# Sheet.net
KiCad netlist of a schematic drawn in Altium Designer
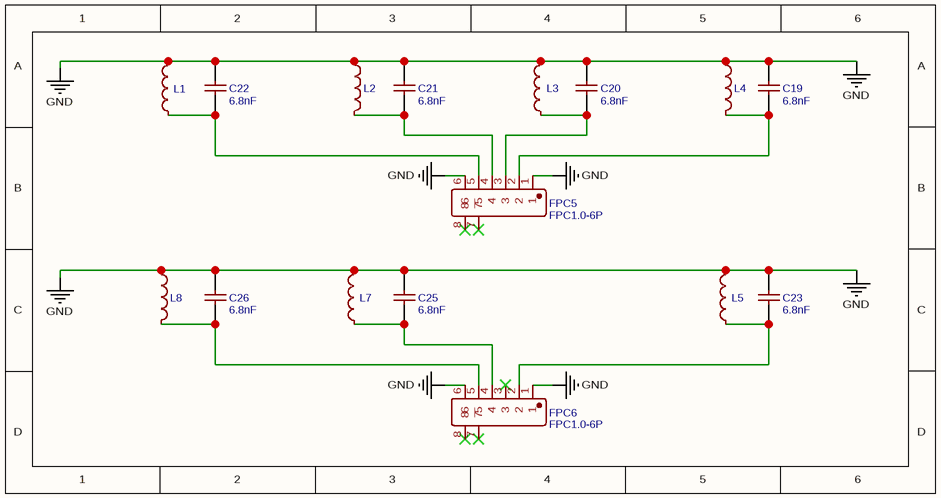
[diagram p0: Sheet_电磁杆.schdoc]

(export (version "E")
  (design (tool "Eeschema 10.0.6"))
  (components
    (comp (ref "C19")
      (value "6.8nF")
      (fields (field (name "MANUFACTURER") "汤姆逊 TPC") (field (name "MANUFACTURER PART") "682J100V"))
      (libsource (lib "altium-import") (part "root_1_6.8nF_"))
    )
    (comp (ref "C20")
      (value "6.8nF")
      (fields (field (name "MANUFACTURER") "汤姆逊 TPC") (field (name "MANUFACTURER PART") "682J100V"))
      (libsource (lib "altium-import") (part "root_1_6.8nF_"))
    )
    (comp (ref "C21")
      (value "6.8nF")
      (fields (field (name "MANUFACTURER") "汤姆逊 TPC") (field (name "MANUFACTURER PART") "682J100V"))
      (libsource (lib "altium-import") (part "root_1_6.8nF_"))
    )
    (comp (ref "C22")
      (value "6.8nF")
      (fields (field (name "MANUFACTURER") "汤姆逊 TPC") (field (name "MANUFACTURER PART") "682J100V"))
      (libsource (lib "altium-import") (part "root_1_6.8nF_"))
    )
    (comp (ref "C23")
      (value "6.8nF")
      (fields (field (name "MANUFACTURER") "汤姆逊 TPC") (field (name "MANUFACTURER PART") "682J100V"))
      (libsource (lib "altium-import") (part "root_1_6.8nF_"))
    )
    (comp (ref "C25")
      (value "6.8nF")
      (fields (field (name "MANUFACTURER") "汤姆逊 TPC") (field (name "MANUFACTURER PART") "682J100V"))
      (libsource (lib "altium-import") (part "root_1_6.8nF_"))
    )
    (comp (ref "C26")
      (value "6.8nF")
      (fields (field (name "MANUFACTURER") "汤姆逊 TPC") (field (name "MANUFACTURER PART") "682J100V"))
      (libsource (lib "altium-import") (part "root_1_6.8nF_"))
    )
    (comp (ref "FPC5")
      (value "FPC1.0-6P")
      (fields
        (field (name "MANUFACTURER") "Ckmtw")
        (field (name "MANUFACTURER PART") "FPC1.0-8P")
        (field (name "CONTRIBUTOR") "zjw101016")
      )
      (libsource (lib "altium-import") (part "root_3_FPC1.0-6P_"))
    )
    (comp (ref "FPC6")
      (value "FPC1.0-6P")
      (fields
        (field (name "MANUFACTURER") "Ckmtw")
        (field (name "MANUFACTURER PART") "FPC1.0-8P")
        (field (name "CONTRIBUTOR") "zjw101016")
      )
      (libsource (lib "altium-import") (part "root_3_FPC1.0-6P_"))
    )
    (comp (ref "L1")
      (value "10mH工字电感")
      (fields (field (name "CONTRIBUTOR") "H_Z_Y"))
      (libsource (lib "altium-import") (part "root_1_10mH工字电感_"))
    )
    (comp (ref "L2")
      (value "10mH工字电感")
      (fields (field (name "CONTRIBUTOR") "H_Z_Y"))
      (libsource (lib "altium-import") (part "root_3_10mH工字电感_"))
    )
    (comp (ref "L3")
      (value "10mH工字电感")
      (fields (field (name "CONTRIBUTOR") "H_Z_Y"))
      (libsource (lib "") (part "root_1_10mH工字电感__2"))
    )
    (comp (ref "L4")
      (value "10mH工字电感")
      (fields (field (name "CONTRIBUTOR") "H_Z_Y"))
      (libsource (lib "") (part "root_3_10mH工字电感__2"))
    )
    (comp (ref "L5")
      (value "10mH工字电感")
      (fields (field (name "CONTRIBUTOR") "H_Z_Y"))
      (libsource (lib "") (part "root_1_10mH工字电感__1"))
    )
    (comp (ref "L7")
      (value "10mH工字电感")
      (fields (field (name "CONTRIBUTOR") "H_Z_Y"))
      (libsource (lib "") (part "root_1_10mH工字电感__3"))
    )
    (comp (ref "L8")
      (value "10mH工字电感")
      (fields (field (name "CONTRIBUTOR") "H_Z_Y"))
      (libsource (lib "") (part "root_3_10mH工字电感__1"))
    )
  )
  (nets
    (net (code "1") (name "GND") (class "Default")
      (node (ref "C19") (pin "2") (pinfunction "2_2") (pintype "passive"))
      (node (ref "C20") (pin "2") (pinfunction "2_2") (pintype "passive"))
      (node (ref "C21") (pin "2") (pinfunction "2_2") (pintype "passive"))
      (node (ref "C22") (pin "2") (pinfunction "2_2") (pintype "passive"))
      (node (ref "C23") (pin "2") (pinfunction "2_2") (pintype "passive"))
      (node (ref "C25") (pin "2") (pinfunction "2_2") (pintype "passive"))
      (node (ref "C26") (pin "2") (pinfunction "2_2") (pintype "passive"))
      (node (ref "FPC5") (pin "1") (pinfunction "1_1") (pintype "passive"))
      (node (ref "FPC5") (pin "6") (pinfunction "6_6") (pintype "passive"))
      (node (ref "FPC6") (pin "1") (pinfunction "1_1") (pintype "passive"))
      (node (ref "FPC6") (pin "6") (pinfunction "6_6") (pintype "passive"))
      (node (ref "L1") (pin "2") (pinfunction "2_2") (pintype "passive"))
      (node (ref "L2") (pin "1") (pinfunction "1_1") (pintype "passive"))
      (node (ref "L3") (pin "2") (pinfunction "2_2") (pintype "passive"))
      (node (ref "L4") (pin "1") (pinfunction "1_1") (pintype "passive"))
      (node (ref "L5") (pin "2") (pinfunction "2_2") (pintype "passive"))
      (node (ref "L7") (pin "2") (pinfunction "2_2") (pintype "passive"))
      (node (ref "L8") (pin "1") (pinfunction "1_1") (pintype "passive"))
    )
    (net (code "2") (name "Net-(C19-Pad1)") (class "Default")
      (node (ref "C19") (pin "1") (pinfunction "1_1") (pintype "passive"))
      (node (ref "FPC5") (pin "2") (pinfunction "2_2") (pintype "passive"))
      (node (ref "L4") (pin "2") (pinfunction "2_2") (pintype "passive"))
    )
    (net (code "3") (name "Net-(C20-Pad1)") (class "Default")
      (node (ref "C20") (pin "1") (pinfunction "1_1") (pintype "passive"))
      (node (ref "FPC5") (pin "3") (pinfunction "3_3") (pintype "passive"))
      (node (ref "L3") (pin "1") (pinfunction "1_1") (pintype "passive"))
    )
    (net (code "4") (name "Net-(C21-Pad1)") (class "Default")
      (node (ref "C21") (pin "1") (pinfunction "1_1") (pintype "passive"))
      (node (ref "FPC5") (pin "4") (pinfunction "4_4") (pintype "passive"))
      (node (ref "L2") (pin "2") (pinfunction "2_2") (pintype "passive"))
    )
    (net (code "5") (name "Net-(C22-Pad1)") (class "Default")
      (node (ref "C22") (pin "1") (pinfunction "1_1") (pintype "passive"))
      (node (ref "FPC5") (pin "5") (pinfunction "5_5") (pintype "passive"))
      (node (ref "L1") (pin "1") (pinfunction "1_1") (pintype "passive"))
    )
    (net (code "6") (name "Net-(C23-Pad1)") (class "Default")
      (node (ref "C23") (pin "1") (pinfunction "1_1") (pintype "passive"))
      (node (ref "FPC6") (pin "2") (pinfunction "2_2") (pintype "passive"))
      (node (ref "L5") (pin "1") (pinfunction "1_1") (pintype "passive"))
    )
    (net (code "7") (name "Net-(C25-Pad1)") (class "Default")
      (node (ref "C25") (pin "1") (pinfunction "1_1") (pintype "passive"))
      (node (ref "FPC6") (pin "4") (pinfunction "4_4") (pintype "passive"))
      (node (ref "L7") (pin "1") (pinfunction "1_1") (pintype "passive"))
    )
    (net (code "8") (name "Net-(C26-Pad1)") (class "Default")
      (node (ref "C26") (pin "1") (pinfunction "1_1") (pintype "passive"))
      (node (ref "FPC6") (pin "5") (pinfunction "5_5") (pintype "passive"))
      (node (ref "L8") (pin "2") (pinfunction "2_2") (pintype "passive"))
    )
    (net (code "9") (name "unconnected-(FPC5-Pad7)") (class "Default")
      (node (ref "FPC5") (pin "7") (pinfunction "7_7") (pintype "passive+no_connect"))
    )
    (net (code "10") (name "unconnected-(FPC5-Pad8)") (class "Default")
      (node (ref "FPC5") (pin "8") (pinfunction "8_8") (pintype "passive+no_connect"))
    )
    (net (code "11") (name "unconnected-(FPC6-Pad3)") (class "Default")
      (node (ref "FPC6") (pin "3") (pinfunction "3_3") (pintype "passive+no_connect"))
    )
    (net (code "12") (name "unconnected-(FPC6-Pad7)") (class "Default")
      (node (ref "FPC6") (pin "7") (pinfunction "7_7") (pintype "passive+no_connect"))
    )
    (net (code "13") (name "unconnected-(FPC6-Pad8)") (class "Default")
      (node (ref "FPC6") (pin "8") (pinfunction "8_8") (pintype "passive+no_connect"))
    )
  )
)
